# 02-FPGA_Banks.net
KiCad netlist of a schematic drawn in Altium Designer
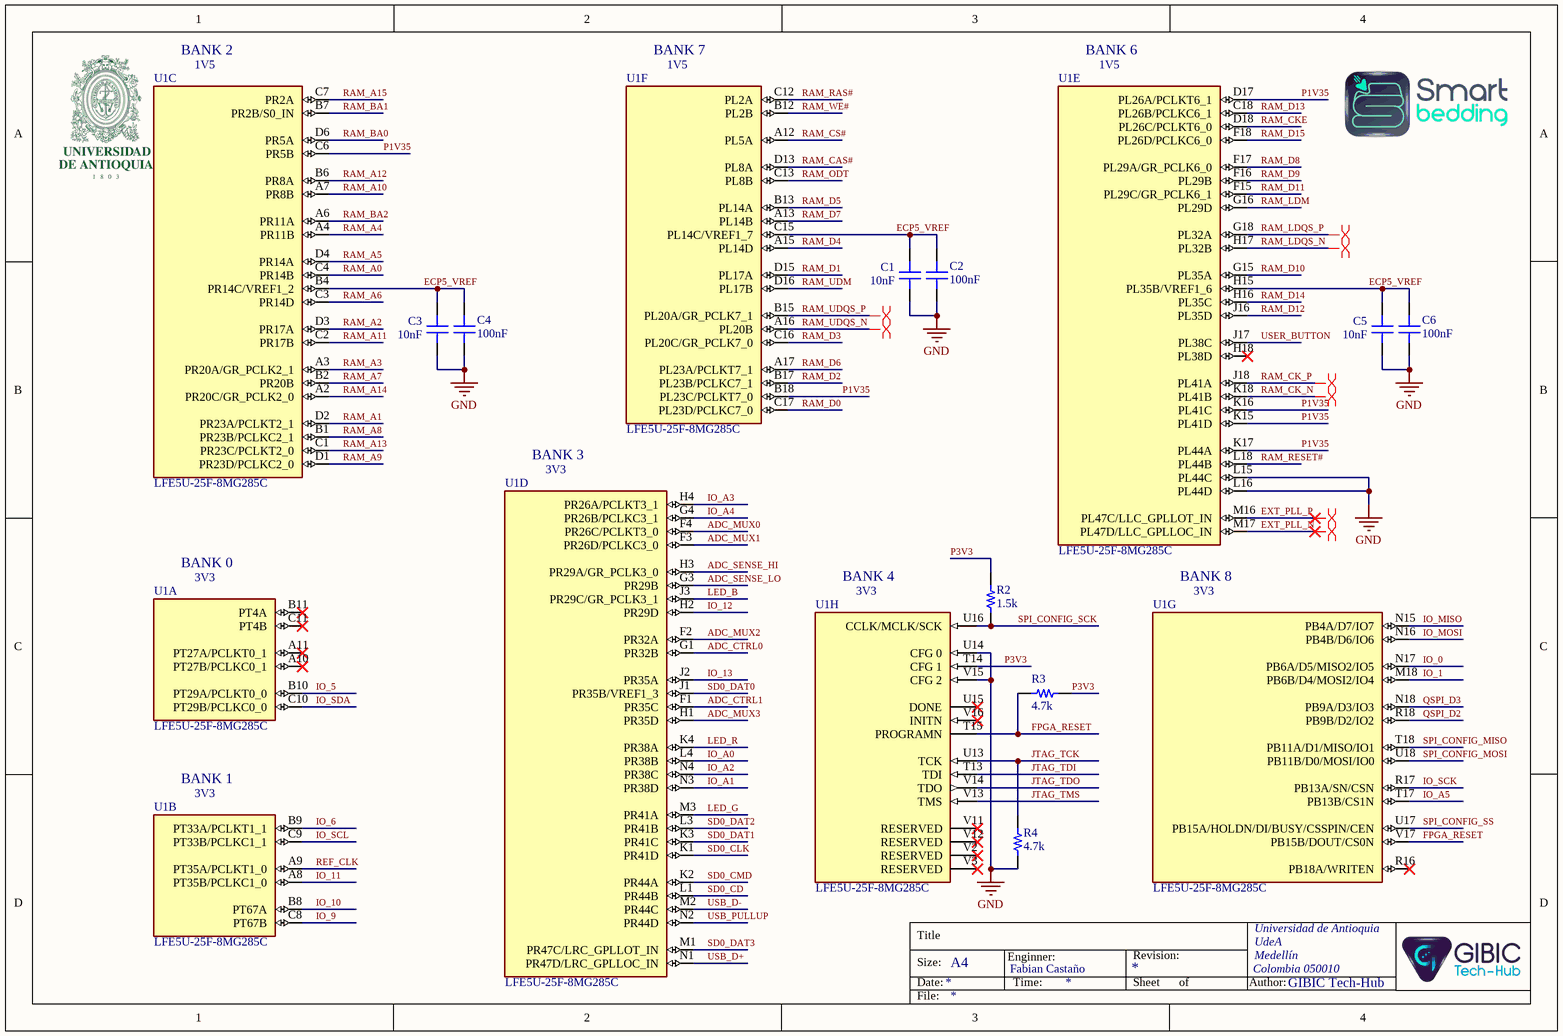
[diagram p0: 02-FPGA_Banks.SchDoc]

(export (version "E")
  (design (tool "Eeschema 10.0.6"))
  (components
    (comp (ref "C1")
      (value "10nF")
      (footprint "CAP 0201_0603")
      (description "CAP CER 10000PF 10V X7R 0201")
      (fields
        (field (name "PART NUMBER") "0201ZC103JAT2A")
        (field (name "MANUFACTURER") "AVX Corporation")
        (field (name "LASTUPDATED") "2/09/2020 12:59:12 a. m.")
      )
      (libsource (lib "Celestial Altium Library - altium_library") (part "Capacitor"))
    )
    (comp (ref "C2")
      (value "100nF")
      (footprint "CAP 0201_0603")
      (description "CAP CER 0.1UF 6.3V X6S 0201")
      (fields
        (field (name "PART NUMBER") "GRT033C80J104KE01J")
        (field (name "MANUFACTURER") "Murata Electronics")
        (field (name "LASTUPDATED") "3/01/2023 8:00:58 p. m.")
      )
      (libsource (lib "Celestial Altium Library - altium_library") (part "Capacitor"))
    )
    (comp (ref "C3")
      (value "10nF")
      (footprint "CAP 0201_0603")
      (description "CAP CER 10000PF 10V X7R 0201")
      (fields
        (field (name "PART NUMBER") "0201ZC103JAT2A")
        (field (name "MANUFACTURER") "AVX Corporation")
        (field (name "LASTUPDATED") "2/09/2020 12:59:12 a. m.")
      )
      (libsource (lib "Celestial Altium Library - altium_library") (part "Capacitor"))
    )
    (comp (ref "C4")
      (value "100nF")
      (footprint "CAP 0201_0603")
      (description "CAP CER 0.1UF 6.3V X6S 0201")
      (fields
        (field (name "PART NUMBER") "GRT033C80J104KE01J")
        (field (name "MANUFACTURER") "Murata Electronics")
        (field (name "LASTUPDATED") "3/01/2023 8:00:58 p. m.")
      )
      (libsource (lib "Celestial Altium Library - altium_library") (part "Capacitor"))
    )
    (comp (ref "C5")
      (value "10nF")
      (footprint "CAP 0201_0603")
      (description "CAP CER 10000PF 10V X7R 0201")
      (fields
        (field (name "PART NUMBER") "0201ZC103JAT2A")
        (field (name "MANUFACTURER") "AVX Corporation")
        (field (name "LASTUPDATED") "2/09/2020 12:59:12 a. m.")
      )
      (libsource (lib "Celestial Altium Library - altium_library") (part "Capacitor"))
    )
    (comp (ref "C6")
      (value "100nF")
      (footprint "CAP 0201_0603")
      (description "CAP CER 0.1UF 6.3V X6S 0201")
      (fields
        (field (name "PART NUMBER") "GRT033C80J104KE01J")
        (field (name "MANUFACTURER") "Murata Electronics")
        (field (name "LASTUPDATED") "3/01/2023 8:00:58 p. m.")
      )
      (libsource (lib "Celestial Altium Library - altium_library") (part "Capacitor"))
    )
    (comp (ref "R2")
      (value "1.5k")
      (footprint "RES 0201_0603")
      (description "RES SMD 10K OHM 0.1% 1/20W 0201")
      (fields
        (field (name "PART NUMBER") "ERA-1AEB103C")
        (field (name "MANUFACTURER") "Panasonic Electronic Components")
        (field (name "LASTUPDATED") "3/01/2023 8:15:23 p. m.")
      )
      (libsource (lib "Celestial Altium Library - altium_library") (part "Resistor"))
    )
    (comp (ref "R3")
      (value "4.7k")
      (footprint "RES 0201_0603")
      (description "RES SMD 10K OHM 0.1% 1/20W 0201")
      (fields
        (field (name "PART NUMBER") "ERA-1AEB103C")
        (field (name "MANUFACTURER") "Panasonic Electronic Components")
        (field (name "LASTUPDATED") "3/01/2023 8:15:23 p. m.")
      )
      (libsource (lib "Celestial Altium Library - altium_library") (part "Resistor"))
    )
    (comp (ref "R4")
      (value "4.7k")
      (footprint "RES 0201_0603")
      (description "RES SMD 10K OHM 0.1% 1/20W 0201")
      (fields
        (field (name "PART NUMBER") "ERA-1AEB103C")
        (field (name "MANUFACTURER") "Panasonic Electronic Components")
        (field (name "LASTUPDATED") "3/01/2023 8:15:23 p. m.")
      )
      (libsource (lib "Celestial Altium Library - altium_library") (part "Resistor"))
    )
    (comp (ref "U1")
      (value "LFE5U-25F-8MG285C")
      (footprint "FP-cBGA-LFE5U")
      (description "FPGA LatticeECP5 Family 24000 Cells 40nm Technology 1.1V 285-Pin CSFBGA")
      (libsource (lib "LFE5U-25F-8MG285C") (part "LFE5U-25F-8MG285C"))
    )
  )
  (nets
    (net (code "1") (name "/ADC_CTRL0") (class "Default")
      (node (ref "U1") (pin "G1") (pinfunction "PR32B_G1") (pintype "bidirectional"))
    )
    (net (code "2") (name "/ADC_CTRL1") (class "Default")
      (node (ref "U1") (pin "F1") (pinfunction "PR35C_F1") (pintype "bidirectional"))
    )
    (net (code "3") (name "/ADC_MUX0") (class "Default")
      (node (ref "U1") (pin "F4") (pinfunction "PR26C/PCLKT3_0_F4") (pintype "bidirectional"))
    )
    (net (code "4") (name "/ADC_MUX1") (class "Default")
      (node (ref "U1") (pin "F3") (pinfunction "PR26D/PCLKC3_0_F3") (pintype "bidirectional"))
    )
    (net (code "5") (name "/ADC_MUX2") (class "Default")
      (node (ref "U1") (pin "F2") (pinfunction "PR32A_F2") (pintype "bidirectional"))
    )
    (net (code "6") (name "/ADC_MUX3") (class "Default")
      (node (ref "U1") (pin "H1") (pinfunction "PR35D_H1") (pintype "bidirectional"))
    )
    (net (code "7") (name "/ADC_SENSE_HI") (class "Default")
      (node (ref "U1") (pin "H3") (pinfunction "PR29A/GR_PCLK3_0_H3") (pintype "bidirectional"))
    )
    (net (code "8") (name "/ADC_SENSE_LO") (class "Default")
      (node (ref "U1") (pin "G3") (pinfunction "PR29B_G3") (pintype "bidirectional"))
    )
    (net (code "9") (name "/ECP5_VREF") (class "Default")
      (node (ref "C1") (pin "2") (pinfunction "2_2") (pintype "passive"))
      (node (ref "C2") (pin "2") (pinfunction "2_2") (pintype "passive"))
      (node (ref "C3") (pin "2") (pinfunction "2_2") (pintype "passive"))
      (node (ref "C4") (pin "2") (pinfunction "2_2") (pintype "passive"))
      (node (ref "C5") (pin "2") (pinfunction "2_2") (pintype "passive"))
      (node (ref "C6") (pin "2") (pinfunction "2_2") (pintype "passive"))
      (node (ref "U1") (pin "B4") (pinfunction "PR14C/VREF1_2_B4") (pintype "bidirectional"))
      (node (ref "U1") (pin "C15") (pinfunction "PL14C/VREF1_7_C15") (pintype "bidirectional"))
      (node (ref "U1") (pin "H15") (pinfunction "PL35B/VREF1_6_H15") (pintype "bidirectional"))
    )
    (net (code "10") (name "/EXT_PLL_N") (class "Default")
      (node (ref "U1") (pin "M17") (pinfunction "PL47D/LLC_GPLLOC_IN_M17") (pintype "bidirectional+no_connect"))
    )
    (net (code "11") (name "/EXT_PLL_P") (class "Default")
      (node (ref "U1") (pin "M16") (pinfunction "PL47C/LLC_GPLLOT_IN_M16") (pintype "bidirectional+no_connect"))
    )
    (net (code "12") (name "/FPGA_RESET") (class "Default")
      (node (ref "R3") (pin "2") (pinfunction "2_2") (pintype "passive"))
      (node (ref "U1") (pin "T15") (pinfunction "PROGRAMN_T15") (pintype "passive"))
      (node (ref "U1") (pin "V17") (pinfunction "PB15B/DOUT/CS0N_V17") (pintype "bidirectional"))
    )
    (net (code "13") (name "/IO_0") (class "Default")
      (node (ref "U1") (pin "N17") (pinfunction "PB6A/D5/MISO2/IO5_N17") (pintype "bidirectional"))
    )
    (net (code "14") (name "/IO_1") (class "Default")
      (node (ref "U1") (pin "M18") (pinfunction "PB6B/D4/MOSI2/IO4_M18") (pintype "bidirectional"))
    )
    (net (code "15") (name "/IO_5") (class "Default")
      (node (ref "U1") (pin "B10") (pinfunction "PT29A/PCLKT0_0_B10") (pintype "bidirectional"))
    )
    (net (code "16") (name "/IO_6") (class "Default")
      (node (ref "U1") (pin "B9") (pinfunction "PT33A/PCLKT1_1_B9") (pintype "bidirectional"))
    )
    (net (code "17") (name "/IO_9") (class "Default")
      (node (ref "U1") (pin "C8") (pinfunction "PT67B_C8") (pintype "bidirectional"))
    )
    (net (code "18") (name "/IO_10") (class "Default")
      (node (ref "U1") (pin "B8") (pinfunction "PT67A_B8") (pintype "bidirectional"))
    )
    (net (code "19") (name "/IO_11") (class "Default")
      (node (ref "U1") (pin "A8") (pinfunction "PT35B/PCLKC1_0_A8") (pintype "bidirectional"))
    )
    (net (code "20") (name "/IO_12") (class "Default")
      (node (ref "U1") (pin "H2") (pinfunction "PR29D_H2") (pintype "bidirectional"))
    )
    (net (code "21") (name "/IO_13") (class "Default")
      (node (ref "U1") (pin "J2") (pinfunction "PR35A_J2") (pintype "bidirectional"))
    )
    (net (code "22") (name "/IO_A0") (class "Default")
      (node (ref "U1") (pin "L4") (pinfunction "PR38B_L4") (pintype "bidirectional"))
    )
    (net (code "23") (name "/IO_A1") (class "Default")
      (node (ref "U1") (pin "N3") (pinfunction "PR38D_N3") (pintype "bidirectional"))
    )
    (net (code "24") (name "/IO_A2") (class "Default")
      (node (ref "U1") (pin "N4") (pinfunction "PR38C_N4") (pintype "bidirectional"))
    )
    (net (code "25") (name "/IO_A3") (class "Default")
      (node (ref "U1") (pin "H4") (pinfunction "PR26A/PCLKT3_1_H4") (pintype "bidirectional"))
    )
    (net (code "26") (name "/IO_A4") (class "Default")
      (node (ref "U1") (pin "G4") (pinfunction "PR26B/PCLKC3_1_G4") (pintype "bidirectional"))
    )
    (net (code "27") (name "/IO_A5") (class "Default")
      (node (ref "U1") (pin "T17") (pinfunction "PB13B/CS1N_T17") (pintype "bidirectional"))
    )
    (net (code "28") (name "/IO_MISO") (class "Default")
      (node (ref "U1") (pin "N15") (pinfunction "PB4A/D7/IO7_N15") (pintype "bidirectional"))
    )
    (net (code "29") (name "/IO_MOSI") (class "Default")
      (node (ref "U1") (pin "N16") (pinfunction "PB4B/D6/IO6_N16") (pintype "bidirectional"))
    )
    (net (code "30") (name "/IO_SCK") (class "Default")
      (node (ref "U1") (pin "R17") (pinfunction "PB13A/SN/CSN_R17") (pintype "bidirectional"))
    )
    (net (code "31") (name "/IO_SCL") (class "Default")
      (node (ref "U1") (pin "C9") (pinfunction "PT33B/PCLKC1_1_C9") (pintype "bidirectional"))
    )
    (net (code "32") (name "/IO_SDA") (class "Default")
      (node (ref "U1") (pin "C10") (pinfunction "PT29B/PCLKC0_0_C10") (pintype "bidirectional"))
    )
    (net (code "33") (name "/JTAG_TCK") (class "Default")
      (node (ref "R4") (pin "1") (pinfunction "1_1") (pintype "passive"))
      (node (ref "U1") (pin "U13") (pinfunction "TCK_U13") (pintype "input"))
    )
    (net (code "34") (name "/JTAG_TDI") (class "Default")
      (node (ref "U1") (pin "T13") (pinfunction "TDI_T13") (pintype "input"))
    )
    (net (code "35") (name "/JTAG_TDO") (class "Default")
      (node (ref "U1") (pin "V14") (pinfunction "TDO_V14") (pintype "output"))
    )
    (net (code "36") (name "/JTAG_TMS") (class "Default")
      (node (ref "U1") (pin "V13") (pinfunction "TMS_V13") (pintype "input"))
    )
    (net (code "37") (name "/LED_B") (class "Default")
      (node (ref "U1") (pin "J3") (pinfunction "PR29C/GR_PCLK3_1_J3") (pintype "bidirectional"))
    )
    (net (code "38") (name "/LED_G") (class "Default")
      (node (ref "U1") (pin "M3") (pinfunction "PR41A_M3") (pintype "bidirectional"))
    )
    (net (code "39") (name "/LED_R") (class "Default")
      (node (ref "U1") (pin "K4") (pinfunction "PR38A_K4") (pintype "bidirectional"))
    )
    (net (code "40") (name "/P1V35") (class "Default")
      (node (ref "U1") (pin "B18") (pinfunction "PL23C/PCLKT7_0_B18") (pintype "bidirectional"))
      (node (ref "U1") (pin "C6") (pinfunction "PR5B_C6") (pintype "bidirectional"))
      (node (ref "U1") (pin "D17") (pinfunction "PL26A/PCLKT6_1_D17") (pintype "bidirectional"))
      (node (ref "U1") (pin "K15") (pinfunction "PL41D_K15") (pintype "bidirectional"))
      (node (ref "U1") (pin "K16") (pinfunction "PL41C_K16") (pintype "bidirectional"))
      (node (ref "U1") (pin "K17") (pinfunction "PL44A_K17") (pintype "bidirectional"))
    )
    (net (code "41") (name "/P3V3") (class "Default")
      (node (ref "R2") (pin "1") (pinfunction "1_1") (pintype "passive"))
      (node (ref "R3") (pin "1") (pinfunction "1_1") (pintype "passive"))
      (node (ref "U1") (pin "T14") (pinfunction "CFG_1_T14") (pintype "input"))
    )
    (net (code "42") (name "/QSPI_D2") (class "Default")
      (node (ref "U1") (pin "R18") (pinfunction "PB9B/D2/IO2_R18") (pintype "bidirectional"))
    )
    (net (code "43") (name "/QSPI_D3") (class "Default")
      (node (ref "U1") (pin "N18") (pinfunction "PB9A/D3/IO3_N18") (pintype "bidirectional"))
    )
    (net (code "44") (name "/RAM_A0") (class "Default")
      (node (ref "U1") (pin "C4") (pinfunction "PR14B_C4") (pintype "bidirectional"))
    )
    (net (code "45") (name "/RAM_A1") (class "Default")
      (node (ref "U1") (pin "D2") (pinfunction "PR23A/PCLKT2_1_D2") (pintype "bidirectional"))
    )
    (net (code "46") (name "/RAM_A2") (class "Default")
      (node (ref "U1") (pin "D3") (pinfunction "PR17A_D3") (pintype "bidirectional"))
    )
    (net (code "47") (name "/RAM_A3") (class "Default")
      (node (ref "U1") (pin "A3") (pinfunction "PR20A/GR_PCLK2_1_A3") (pintype "bidirectional"))
    )
    (net (code "48") (name "/RAM_A4") (class "Default")
      (node (ref "U1") (pin "A4") (pinfunction "PR11B_A4") (pintype "bidirectional"))
    )
    (net (code "49") (name "/RAM_A5") (class "Default")
      (node (ref "U1") (pin "D4") (pinfunction "PR14A_D4") (pintype "bidirectional"))
    )
    (net (code "50") (name "/RAM_A6") (class "Default")
      (node (ref "U1") (pin "C3") (pinfunction "PR14D_C3") (pintype "bidirectional"))
    )
    (net (code "51") (name "/RAM_A7") (class "Default")
      (node (ref "U1") (pin "B2") (pinfunction "PR20B_B2") (pintype "bidirectional"))
    )
    (net (code "52") (name "/RAM_A8") (class "Default")
      (node (ref "U1") (pin "B1") (pinfunction "PR23B/PCLKC2_1_B1") (pintype "bidirectional"))
    )
    (net (code "53") (name "/RAM_A9") (class "Default")
      (node (ref "U1") (pin "D1") (pinfunction "PR23D/PCLKC2_0_D1") (pintype "bidirectional"))
    )
    (net (code "54") (name "/RAM_A10") (class "Default")
      (node (ref "U1") (pin "A7") (pinfunction "PR8B_A7") (pintype "bidirectional"))
    )
    (net (code "55") (name "/RAM_A11") (class "Default")
      (node (ref "U1") (pin "C2") (pinfunction "PR17B_C2") (pintype "bidirectional"))
    )
    (net (code "56") (name "/RAM_A12") (class "Default")
      (node (ref "U1") (pin "B6") (pinfunction "PR8A_B6") (pintype "bidirectional"))
    )
    (net (code "57") (name "/RAM_A13") (class "Default")
      (node (ref "U1") (pin "C1") (pinfunction "PR23C/PCLKT2_0_C1") (pintype "bidirectional"))
    )
    (net (code "58") (name "/RAM_A14") (class "Default")
      (node (ref "U1") (pin "A2") (pinfunction "PR20C/GR_PCLK2_0_A2") (pintype "bidirectional"))
    )
    (net (code "59") (name "/RAM_A15") (class "Default")
      (node (ref "U1") (pin "C7") (pinfunction "PR2A_C7") (pintype "bidirectional"))
    )
    (net (code "60") (name "/RAM_BA0") (class "Default")
      (node (ref "U1") (pin "D6") (pinfunction "PR5A_D6") (pintype "bidirectional"))
    )
    (net (code "61") (name "/RAM_BA1") (class "Default")
      (node (ref "U1") (pin "B7") (pinfunction "PR2B/S0_IN_B7") (pintype "bidirectional"))
    )
    (net (code "62") (name "/RAM_BA2") (class "Default")
      (node (ref "U1") (pin "A6") (pinfunction "PR11A_A6") (pintype "bidirectional"))
    )
    (net (code "63") (name "/RAM_CAS#") (class "Default")
      (node (ref "U1") (pin "D13") (pinfunction "PL8A_D13") (pintype "bidirectional"))
    )
    (net (code "64") (name "/RAM_CKE") (class "Default")
      (node (ref "U1") (pin "D18") (pinfunction "PL26C/PCLKT6_0_D18") (pintype "bidirectional"))
    )
    (net (code "65") (name "/RAM_CK_N") (class "Default")
      (node (ref "U1") (pin "K18") (pinfunction "PL41B_K18") (pintype "bidirectional"))
    )
    (net (code "66") (name "/RAM_CK_P") (class "Default")
      (node (ref "U1") (pin "J18") (pinfunction "PL41A_J18") (pintype "bidirectional"))
    )
    (net (code "67") (name "/RAM_CS#") (class "Default")
      (node (ref "U1") (pin "A12") (pinfunction "PL5A_A12") (pintype "bidirectional"))
    )
    (net (code "68") (name "/RAM_D0") (class "Default")
      (node (ref "U1") (pin "C17") (pinfunction "PL23D/PCLKC7_0_C17") (pintype "bidirectional"))
    )
    (net (code "69") (name "/RAM_D1") (class "Default")
      (node (ref "U1") (pin "D15") (pinfunction "PL17A_D15") (pintype "bidirectional"))
    )
    (net (code "70") (name "/RAM_D2") (class "Default")
      (node (ref "U1") (pin "B17") (pinfunction "PL23B/PCLKC7_1_B17") (pintype "bidirectional"))
    )
    (net (code "71") (name "/RAM_D3") (class "Default")
      (node (ref "U1") (pin "C16") (pinfunction "PL20C/GR_PCLK7_0_C16") (pintype "bidirectional"))
    )
    (net (code "72") (name "/RAM_D4") (class "Default")
      (node (ref "U1") (pin "A15") (pinfunction "PL14D_A15") (pintype "bidirectional"))
    )
    (net (code "73") (name "/RAM_D5") (class "Default")
      (node (ref "U1") (pin "B13") (pinfunction "PL14A_B13") (pintype "bidirectional"))
    )
    (net (code "74") (name "/RAM_D6") (class "Default")
      (node (ref "U1") (pin "A17") (pinfunction "PL23A/PCLKT7_1_A17") (pintype "bidirectional"))
    )
    (net (code "75") (name "/RAM_D7") (class "Default")
      (node (ref "U1") (pin "A13") (pinfunction "PL14B_A13") (pintype "bidirectional"))
    )
    (net (code "76") (name "/RAM_D8") (class "Default")
      (node (ref "U1") (pin "F17") (pinfunction "PL29A/GR_PCLK6_0_F17") (pintype "bidirectional"))
    )
    (net (code "77") (name "/RAM_D9") (class "Default")
      (node (ref "U1") (pin "F16") (pinfunction "PL29B_F16") (pintype "bidirectional"))
    )
    (net (code "78") (name "/RAM_D10") (class "Default")
      (node (ref "U1") (pin "G15") (pinfunction "PL35A_G15") (pintype "bidirectional"))
    )
    (net (code "79") (name "/RAM_D11") (class "Default")
      (node (ref "U1") (pin "F15") (pinfunction "PL29C/GR_PCLK6_1_F15") (pintype "bidirectional"))
    )
    (net (code "80") (name "/RAM_D12") (class "Default")
      (node (ref "U1") (pin "J16") (pinfunction "PL35D_J16") (pintype "bidirectional"))
    )
    (net (code "81") (name "/RAM_D13") (class "Default")
      (node (ref "U1") (pin "C18") (pinfunction "PL26B/PCLKC6_1_C18") (pintype "bidirectional"))
    )
    (net (code "82") (name "/RAM_D14") (class "Default")
      (node (ref "U1") (pin "H16") (pinfunction "PL35C_H16") (pintype "bidirectional"))
    )
    (net (code "83") (name "/RAM_D15") (class "Default")
      (node (ref "U1") (pin "F18") (pinfunction "PL26D/PCLKC6_0_F18") (pintype "bidirectional"))
    )
    (net (code "84") (name "/RAM_LDM") (class "Default")
      (node (ref "U1") (pin "G16") (pinfunction "PL29D_G16") (pintype "bidirectional"))
    )
    (net (code "85") (name "/RAM_LDQS_N") (class "Default")
      (node (ref "U1") (pin "H17") (pinfunction "PL32B_H17") (pintype "bidirectional"))
    )
    (net (code "86") (name "/RAM_LDQS_P") (class "Default")
      (node (ref "U1") (pin "G18") (pinfunction "PL32A_G18") (pintype "bidirectional"))
    )
    (net (code "87") (name "/RAM_ODT") (class "Default")
      (node (ref "U1") (pin "C13") (pinfunction "PL8B_C13") (pintype "bidirectional"))
    )
    (net (code "88") (name "/RAM_RAS#") (class "Default")
      (node (ref "U1") (pin "C12") (pinfunction "PL2A_C12") (pintype "bidirectional"))
    )
    (net (code "89") (name "/RAM_RESET#") (class "Default")
      (node (ref "U1") (pin "L18") (pinfunction "PL44B_L18") (pintype "bidirectional"))
    )
    (net (code "90") (name "/RAM_UDM") (class "Default")
      (node (ref "U1") (pin "D16") (pinfunction "PL17B_D16") (pintype "bidirectional"))
    )
    (net (code "91") (name "/RAM_UDQS_N") (class "Default")
      (node (ref "U1") (pin "A16") (pinfunction "PL20B_A16") (pintype "bidirectional"))
    )
    (net (code "92") (name "/RAM_UDQS_P") (class "Default")
      (node (ref "U1") (pin "B15") (pinfunction "PL20A/GR_PCLK7_1_B15") (pintype "bidirectional"))
    )
    (net (code "93") (name "/RAM_WE#") (class "Default")
      (node (ref "U1") (pin "B12") (pinfunction "PL2B_B12") (pintype "bidirectional"))
    )
    (net (code "94") (name "/REF_CLK") (class "Default")
      (node (ref "U1") (pin "A9") (pinfunction "PT35A/PCLKT1_0_A9") (pintype "bidirectional"))
    )
    (net (code "95") (name "/SD0_CD") (class "Default")
      (node (ref "U1") (pin "L1") (pinfunction "PR44B_L1") (pintype "bidirectional"))
    )
    (net (code "96") (name "/SD0_CLK") (class "Default")
      (node (ref "U1") (pin "K1") (pinfunction "PR41D_K1") (pintype "bidirectional"))
    )
    (net (code "97") (name "/SD0_CMD") (class "Default")
      (node (ref "U1") (pin "K2") (pinfunction "PR44A_K2") (pintype "bidirectional"))
    )
    (net (code "98") (name "/SD0_DAT0") (class "Default")
      (node (ref "U1") (pin "J1") (pinfunction "PR35B/VREF1_3_J1") (pintype "bidirectional"))
    )
    (net (code "99") (name "/SD0_DAT1") (class "Default")
      (node (ref "U1") (pin "K3") (pinfunction "PR41C_K3") (pintype "bidirectional"))
    )
    (net (code "100") (name "/SD0_DAT2") (class "Default")
      (node (ref "U1") (pin "L3") (pinfunction "PR41B_L3") (pintype "bidirectional"))
    )
    (net (code "101") (name "/SD0_DAT3") (class "Default")
      (node (ref "U1") (pin "M1") (pinfunction "PR47C/LRC_GPLLOT_IN_M1") (pintype "bidirectional"))
    )
    (net (code "102") (name "/SPI_CONFIG_MISO") (class "Default")
      (node (ref "U1") (pin "T18") (pinfunction "PB11A/D1/MISO/IO1_T18") (pintype "bidirectional"))
    )
    (net (code "103") (name "/SPI_CONFIG_MOSI") (class "Default")
      (node (ref "U1") (pin "U18") (pinfunction "PB11B/D0/MOSI/IO0_U18") (pintype "bidirectional"))
    )
    (net (code "104") (name "/SPI_CONFIG_SCK") (class "Default")
      (node (ref "R2") (pin "2") (pinfunction "2_2") (pintype "passive"))
      (node (ref "U1") (pin "U16") (pinfunction "CCLK/MCLK/SCK_U16") (pintype "input"))
    )
    (net (code "105") (name "/SPI_CONFIG_SS") (class "Default")
      (node (ref "U1") (pin "U17") (pinfunction "PB15A/HOLDN/DI/BUSY/CSSPIN/CEN_U17") (pintype "bidirectional"))
    )
    (net (code "106") (name "/USB_D+") (class "Default")
      (node (ref "U1") (pin "N1") (pinfunction "PR47D/LRC_GPLLOC_IN_N1") (pintype "bidirectional"))
    )
    (net (code "107") (name "/USB_D-") (class "Default")
      (node (ref "U1") (pin "M2") (pinfunction "PR44C_M2") (pintype "bidirectional"))
    )
    (net (code "108") (name "/USB_PULLUP") (class "Default")
      (node (ref "U1") (pin "N2") (pinfunction "PR44D_N2") (pintype "bidirectional"))
    )
    (net (code "109") (name "/USER_BUTTON") (class "Default")
      (node (ref "U1") (pin "J17") (pinfunction "PL38C_J17") (pintype "bidirectional"))
    )
    (net (code "110") (name "GND") (class "Default")
      (node (ref "C1") (pin "1") (pinfunction "1_1") (pintype "passive"))
      (node (ref "C2") (pin "1") (pinfunction "1_1") (pintype "passive"))
      (node (ref "C3") (pin "1") (pinfunction "1_1") (pintype "passive"))
      (node (ref "C4") (pin "1") (pinfunction "1_1") (pintype "passive"))
      (node (ref "C5") (pin "1") (pinfunction "1_1") (pintype "passive"))
      (node (ref "C6") (pin "1") (pinfunction "1_1") (pintype "passive"))
      (node (ref "R4") (pin "2") (pinfunction "2_2") (pintype "passive"))
      (node (ref "U1") (pin "L15") (pinfunction "PL44C_L15") (pintype "bidirectional"))
      (node (ref "U1") (pin "L16") (pinfunction "PL44D_L16") (pintype "bidirectional"))
      (node (ref "U1") (pin "U14") (pinfunction "CFG_0_U14") (pintype "input"))
      (node (ref "U1") (pin "V15") (pinfunction "CFG_2_V15") (pintype "input"))
    )
    (net (code "111") (name "unconnected-(U1A-PT4A-PadB11)") (class "Default")
      (node (ref "U1") (pin "B11") (pinfunction "PT4A_B11") (pintype "bidirectional+no_connect"))
    )
    (net (code "112") (name "unconnected-(U1A-PT4B-PadC11)") (class "Default")
      (node (ref "U1") (pin "C11") (pinfunction "PT4B_C11") (pintype "bidirectional+no_connect"))
    )
    (net (code "113") (name "unconnected-(U1A-PT27A{slash}PCLKT0_1-PadA11)") (class "Default")
      (node (ref "U1") (pin "A11") (pinfunction "PT27A/PCLKT0_1_A11") (pintype "bidirectional+no_connect"))
    )
    (net (code "114") (name "unconnected-(U1A-PT27B{slash}PCLKC0_1-PadA10)") (class "Default")
      (node (ref "U1") (pin "A10") (pinfunction "PT27B/PCLKC0_1_A10") (pintype "bidirectional+no_connect"))
    )
    (net (code "115") (name "unconnected-(U1E-PL38D-PadH18)") (class "Default")
      (node (ref "U1") (pin "H18") (pinfunction "PL38D_H18") (pintype "bidirectional+no_connect"))
    )
    (net (code "116") (name "unconnected-(U1G-PB18A{slash}WRITEN-PadR16)") (class "Default")
      (node (ref "U1") (pin "R16") (pinfunction "PB18A/WRITEN_R16") (pintype "bidirectional+no_connect"))
    )
    (net (code "117") (name "unconnected-(U1H-DONE-PadU15)") (class "Default")
      (node (ref "U1") (pin "U15") (pinfunction "DONE_U15") (pintype "passive+no_connect"))
    )
    (net (code "118") (name "unconnected-(U1H-INITN-PadV16)") (class "Default")
      (node (ref "U1") (pin "V16") (pinfunction "INITN_V16") (pintype "input+no_connect"))
    )
    (net (code "119") (name "unconnected-(U1H-RESERVED-PadV2)") (class "Default")
      (node (ref "U1") (pin "V2") (pinfunction "RESERVED_V2") (pintype "passive+no_connect"))
    )
    (net (code "120") (name "unconnected-(U1H-RESERVED-PadV3)") (class "Default")
      (node (ref "U1") (pin "V3") (pinfunction "RESERVED_V3") (pintype "passive+no_connect"))
    )
    (net (code "121") (name "unconnected-(U1H-RESERVED-PadV11)") (class "Default")
      (node (ref "U1") (pin "V11") (pinfunction "RESERVED_V11") (pintype "passive+no_connect"))
    )
    (net (code "122") (name "unconnected-(U1H-RESERVED-PadV12)") (class "Default")
      (node (ref "U1") (pin "V12") (pinfunction "RESERVED_V12") (pintype "passive+no_connect"))
    )
  )
)
